# bffSquad.net
KiCad netlist of a schematic drawn in EAGLE
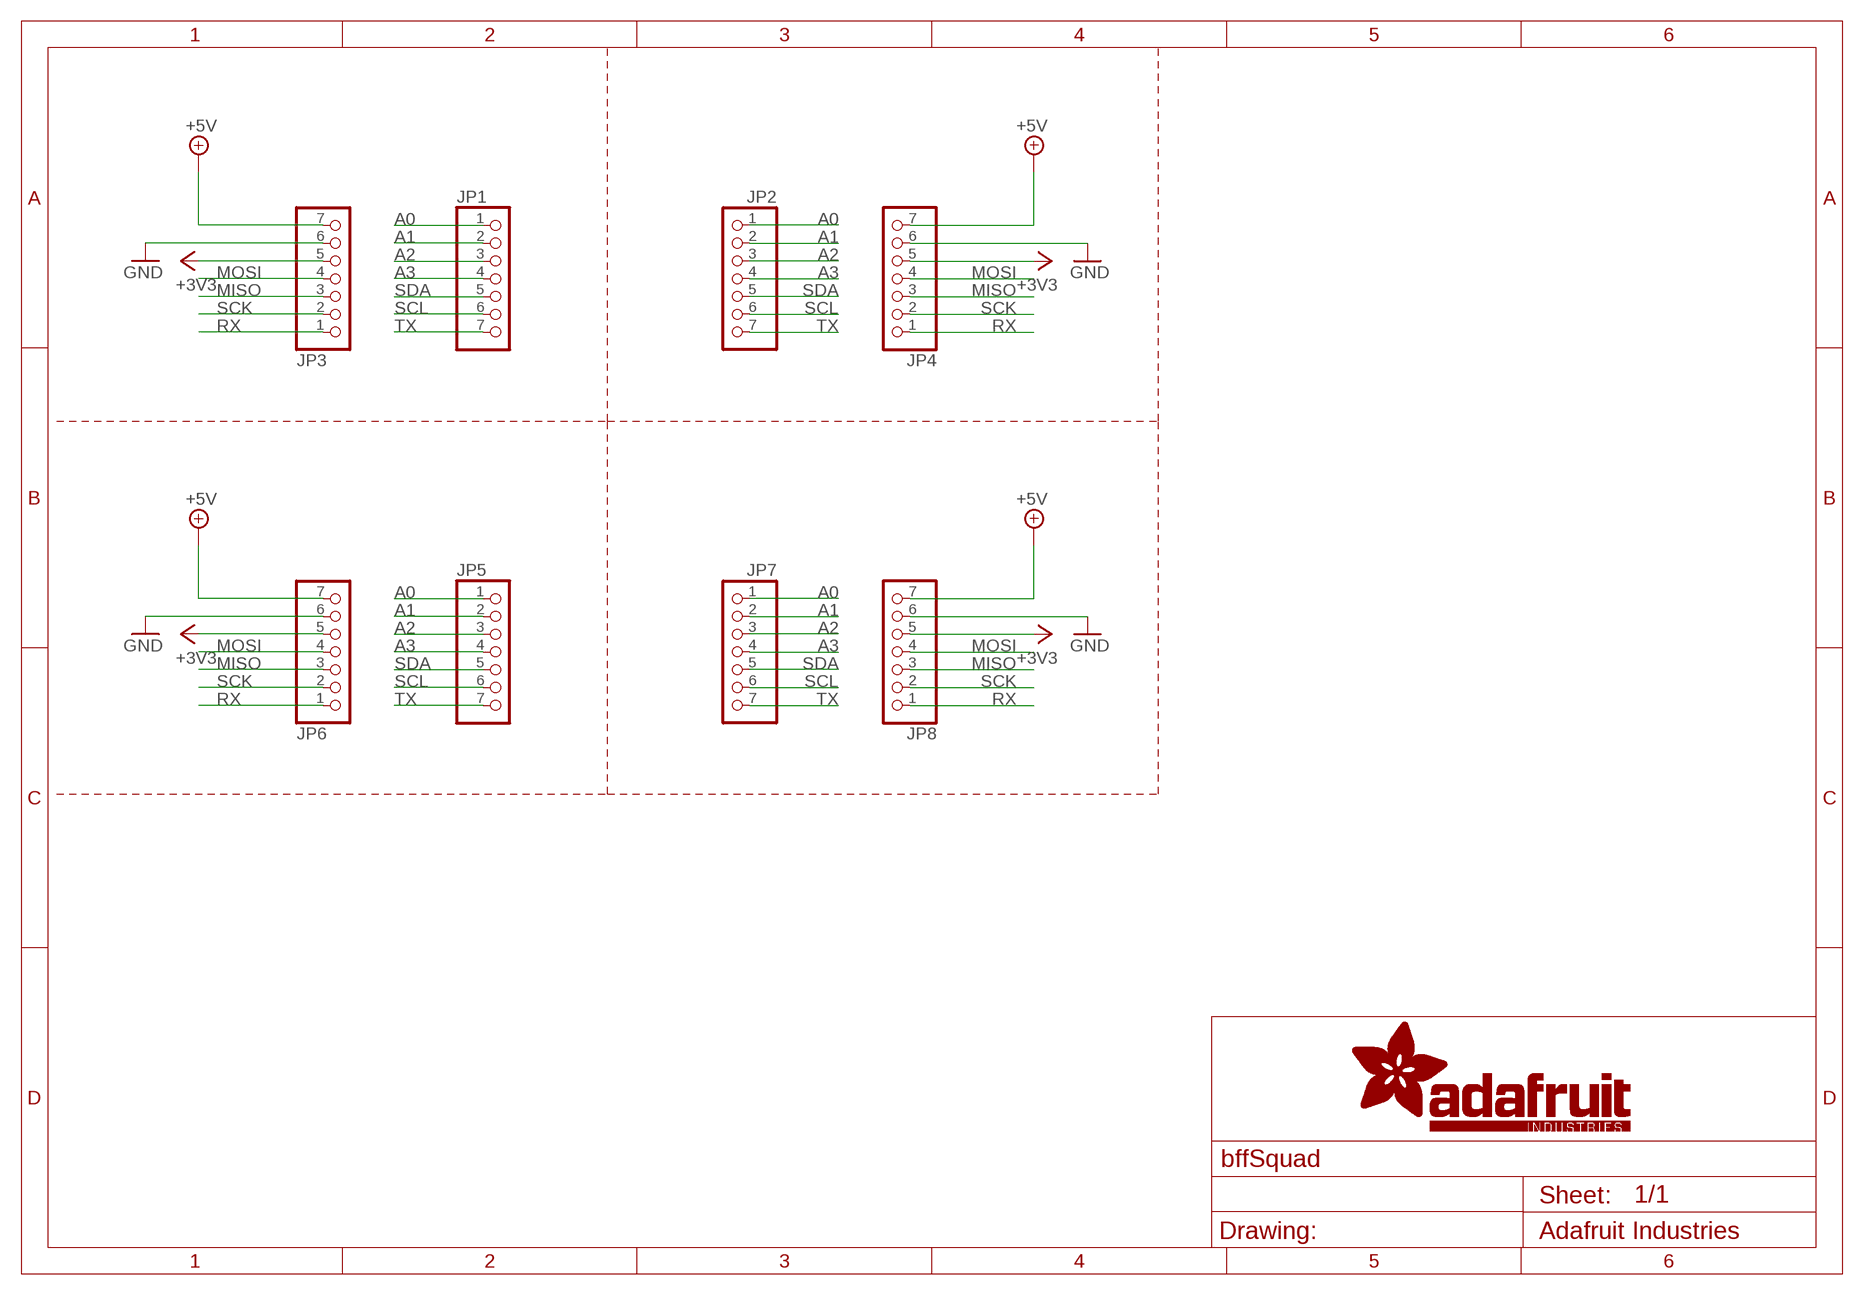
[diagram p0: schematic, sheet 1]

(export (version "E")
  (design (tool "Eeschema 10.0.6"))
  (components
    (comp (ref "JP1")
      (value "HEADER-1X7ROUND")
      (footprint "eagle-import:1X07_ROUND")
      (libsource (lib "eagle-import") (part "HEADER-1X7ROUND"))
    )
    (comp (ref "JP2")
      (value "HEADER-1X7ROUND")
      (footprint "eagle-import:1X07_ROUND")
      (libsource (lib "eagle-import") (part "HEADER-1X7ROUND"))
    )
    (comp (ref "JP3")
      (value "HEADER-1X7ROUND")
      (footprint "eagle-import:1X07_ROUND")
      (libsource (lib "eagle-import") (part "HEADER-1X7ROUND"))
    )
    (comp (ref "JP4")
      (value "HEADER-1X7ROUND")
      (footprint "eagle-import:1X07_ROUND")
      (libsource (lib "eagle-import") (part "HEADER-1X7ROUND"))
    )
    (comp (ref "JP5")
      (value "HEADER-1X7ROUND")
      (footprint "eagle-import:1X07_ROUND")
      (libsource (lib "eagle-import") (part "HEADER-1X7ROUND"))
    )
    (comp (ref "JP6")
      (value "HEADER-1X7ROUND")
      (footprint "eagle-import:1X07_ROUND")
      (libsource (lib "eagle-import") (part "HEADER-1X7ROUND"))
    )
    (comp (ref "JP7")
      (value "HEADER-1X7ROUND")
      (footprint "eagle-import:1X07_ROUND")
      (libsource (lib "eagle-import") (part "HEADER-1X7ROUND"))
    )
    (comp (ref "JP8")
      (value "HEADER-1X7ROUND")
      (footprint "eagle-import:1X07_ROUND")
      (libsource (lib "eagle-import") (part "HEADER-1X7ROUND"))
    )
  )
  (nets
    (net (code "1") (name "+3V3") (class "Default")
      (node (ref "JP3") (pin "5") (pinfunction "5_5") (pintype "passive"))
      (node (ref "JP4") (pin "5") (pinfunction "5_5") (pintype "passive"))
      (node (ref "JP6") (pin "5") (pinfunction "5_5") (pintype "passive"))
      (node (ref "JP8") (pin "5") (pinfunction "5_5") (pintype "passive"))
    )
    (net (code "2") (name "+5V") (class "Default")
      (node (ref "JP3") (pin "7") (pinfunction "7_7") (pintype "passive"))
      (node (ref "JP4") (pin "7") (pinfunction "7_7") (pintype "passive"))
      (node (ref "JP6") (pin "7") (pinfunction "7_7") (pintype "passive"))
      (node (ref "JP8") (pin "7") (pinfunction "7_7") (pintype "passive"))
    )
    (net (code "3") (name "/A0") (class "Default")
      (node (ref "JP1") (pin "1") (pinfunction "1_1") (pintype "passive"))
      (node (ref "JP2") (pin "1") (pinfunction "1_1") (pintype "passive"))
      (node (ref "JP5") (pin "1") (pinfunction "1_1") (pintype "passive"))
      (node (ref "JP7") (pin "1") (pinfunction "1_1") (pintype "passive"))
    )
    (net (code "4") (name "/A1") (class "Default")
      (node (ref "JP1") (pin "2") (pinfunction "2_2") (pintype "passive"))
      (node (ref "JP2") (pin "2") (pinfunction "2_2") (pintype "passive"))
      (node (ref "JP5") (pin "2") (pinfunction "2_2") (pintype "passive"))
      (node (ref "JP7") (pin "2") (pinfunction "2_2") (pintype "passive"))
    )
    (net (code "5") (name "/A2") (class "Default")
      (node (ref "JP1") (pin "3") (pinfunction "3_3") (pintype "passive"))
      (node (ref "JP2") (pin "3") (pinfunction "3_3") (pintype "passive"))
      (node (ref "JP5") (pin "3") (pinfunction "3_3") (pintype "passive"))
      (node (ref "JP7") (pin "3") (pinfunction "3_3") (pintype "passive"))
    )
    (net (code "6") (name "/A3") (class "Default")
      (node (ref "JP1") (pin "4") (pinfunction "4_4") (pintype "passive"))
      (node (ref "JP2") (pin "4") (pinfunction "4_4") (pintype "passive"))
      (node (ref "JP5") (pin "4") (pinfunction "4_4") (pintype "passive"))
      (node (ref "JP7") (pin "4") (pinfunction "4_4") (pintype "passive"))
    )
    (net (code "7") (name "/MISO") (class "Default")
      (node (ref "JP3") (pin "3") (pinfunction "3_3") (pintype "passive"))
      (node (ref "JP4") (pin "3") (pinfunction "3_3") (pintype "passive"))
      (node (ref "JP6") (pin "3") (pinfunction "3_3") (pintype "passive"))
      (node (ref "JP8") (pin "3") (pinfunction "3_3") (pintype "passive"))
    )
    (net (code "8") (name "/MOSI") (class "Default")
      (node (ref "JP3") (pin "4") (pinfunction "4_4") (pintype "passive"))
      (node (ref "JP4") (pin "4") (pinfunction "4_4") (pintype "passive"))
      (node (ref "JP6") (pin "4") (pinfunction "4_4") (pintype "passive"))
      (node (ref "JP8") (pin "4") (pinfunction "4_4") (pintype "passive"))
    )
    (net (code "9") (name "/RX") (class "Default")
      (node (ref "JP3") (pin "1") (pinfunction "1_1") (pintype "passive"))
      (node (ref "JP4") (pin "1") (pinfunction "1_1") (pintype "passive"))
      (node (ref "JP6") (pin "1") (pinfunction "1_1") (pintype "passive"))
      (node (ref "JP8") (pin "1") (pinfunction "1_1") (pintype "passive"))
    )
    (net (code "10") (name "/SCK") (class "Default")
      (node (ref "JP3") (pin "2") (pinfunction "2_2") (pintype "passive"))
      (node (ref "JP4") (pin "2") (pinfunction "2_2") (pintype "passive"))
      (node (ref "JP6") (pin "2") (pinfunction "2_2") (pintype "passive"))
      (node (ref "JP8") (pin "2") (pinfunction "2_2") (pintype "passive"))
    )
    (net (code "11") (name "/SCL") (class "Default")
      (node (ref "JP1") (pin "6") (pinfunction "6_6") (pintype "passive"))
      (node (ref "JP2") (pin "6") (pinfunction "6_6") (pintype "passive"))
      (node (ref "JP5") (pin "6") (pinfunction "6_6") (pintype "passive"))
      (node (ref "JP7") (pin "6") (pinfunction "6_6") (pintype "passive"))
    )
    (net (code "12") (name "/SDA") (class "Default")
      (node (ref "JP1") (pin "5") (pinfunction "5_5") (pintype "passive"))
      (node (ref "JP2") (pin "5") (pinfunction "5_5") (pintype "passive"))
      (node (ref "JP5") (pin "5") (pinfunction "5_5") (pintype "passive"))
      (node (ref "JP7") (pin "5") (pinfunction "5_5") (pintype "passive"))
    )
    (net (code "13") (name "/TX") (class "Default")
      (node (ref "JP1") (pin "7") (pinfunction "7_7") (pintype "passive"))
      (node (ref "JP2") (pin "7") (pinfunction "7_7") (pintype "passive"))
      (node (ref "JP5") (pin "7") (pinfunction "7_7") (pintype "passive"))
      (node (ref "JP7") (pin "7") (pinfunction "7_7") (pintype "passive"))
    )
    (net (code "14") (name "GND") (class "Default")
      (node (ref "JP3") (pin "6") (pinfunction "6_6") (pintype "passive"))
      (node (ref "JP4") (pin "6") (pinfunction "6_6") (pintype "passive"))
      (node (ref "JP6") (pin "6") (pinfunction "6_6") (pintype "passive"))
      (node (ref "JP8") (pin "6") (pinfunction "6_6") (pintype "passive"))
    )
  )
)
